# LED_letter_H.net
KiCad netlist of a schematic drawn in EAGLE
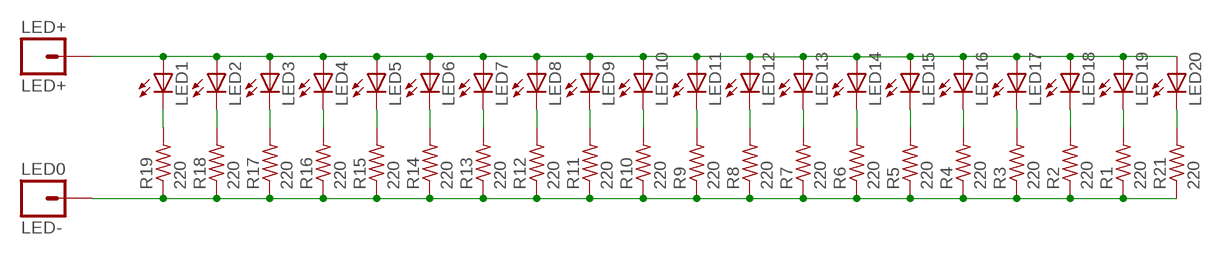
[diagram p0: schematic, sheet 1]

(export (version "E")
  (design (tool "Eeschema 10.0.6"))
  (components
    (comp (ref "LED+")
      (value "LED+")
      (footprint "eagle-import:1X01_OFFSET")
      (libsource (lib "eagle-import") (part "M01OFFSET"))
    )
    (comp (ref "LED0")
      (value "LED-")
      (footprint "eagle-import:1X01_OFFSET")
      (libsource (lib "eagle-import") (part "M01OFFSET"))
    )
    (comp (ref "LED1")
      (value "LED5MM")
      (footprint "eagle-import:LED5MM")
      (libsource (lib "eagle-import") (part "LED5MM"))
    )
    (comp (ref "LED2")
      (value "LED5MM")
      (footprint "eagle-import:LED5MM")
      (libsource (lib "eagle-import") (part "LED5MM"))
    )
    (comp (ref "LED3")
      (value "LED5MM")
      (footprint "eagle-import:LED5MM")
      (libsource (lib "eagle-import") (part "LED5MM"))
    )
    (comp (ref "LED4")
      (value "LED5MM")
      (footprint "eagle-import:LED5MM")
      (libsource (lib "eagle-import") (part "LED5MM"))
    )
    (comp (ref "LED5")
      (value "LED5MM")
      (footprint "eagle-import:LED5MM")
      (libsource (lib "eagle-import") (part "LED5MM"))
    )
    (comp (ref "LED6")
      (value "LED5MM")
      (footprint "eagle-import:LED5MM")
      (libsource (lib "eagle-import") (part "LED5MM"))
    )
    (comp (ref "LED7")
      (value "LED5MM")
      (footprint "eagle-import:LED5MM")
      (libsource (lib "eagle-import") (part "LED5MM"))
    )
    (comp (ref "LED8")
      (value "LED5MM")
      (footprint "eagle-import:LED5MM")
      (libsource (lib "eagle-import") (part "LED5MM"))
    )
    (comp (ref "LED9")
      (value "LED5MM")
      (footprint "eagle-import:LED5MM")
      (libsource (lib "eagle-import") (part "LED5MM"))
    )
    (comp (ref "LED10")
      (value "LED5MM")
      (footprint "eagle-import:LED5MM")
      (libsource (lib "eagle-import") (part "LED5MM"))
    )
    (comp (ref "LED11")
      (value "LED5MM")
      (footprint "eagle-import:LED5MM")
      (libsource (lib "eagle-import") (part "LED5MM"))
    )
    (comp (ref "LED12")
      (value "LED5MM")
      (footprint "eagle-import:LED5MM")
      (libsource (lib "eagle-import") (part "LED5MM"))
    )
    (comp (ref "LED13")
      (value "LED5MM")
      (footprint "eagle-import:LED5MM")
      (libsource (lib "eagle-import") (part "LED5MM"))
    )
    (comp (ref "LED14")
      (value "LED5MM")
      (footprint "eagle-import:LED5MM")
      (libsource (lib "eagle-import") (part "LED5MM"))
    )
    (comp (ref "LED15")
      (value "LED5MM")
      (footprint "eagle-import:LED5MM")
      (libsource (lib "eagle-import") (part "LED5MM"))
    )
    (comp (ref "LED16")
      (value "LED5MM")
      (footprint "eagle-import:LED5MM")
      (libsource (lib "eagle-import") (part "LED5MM"))
    )
    (comp (ref "LED17")
      (value "LED5MM")
      (footprint "eagle-import:LED5MM")
      (libsource (lib "eagle-import") (part "LED5MM"))
    )
    (comp (ref "LED18")
      (value "LED5MM")
      (footprint "eagle-import:LED5MM")
      (libsource (lib "eagle-import") (part "LED5MM"))
    )
    (comp (ref "LED19")
      (value "LED5MM")
      (footprint "eagle-import:LED5MM")
      (libsource (lib "eagle-import") (part "LED5MM"))
    )
    (comp (ref "LED20")
      (value "LED5MM")
      (footprint "eagle-import:LED5MM")
      (libsource (lib "eagle-import") (part "LED5MM"))
    )
    (comp (ref "R1")
      (value "220")
      (footprint "eagle-import:0207_10")
      (libsource (lib "eagle-import") (part "R-US_0207/10"))
    )
    (comp (ref "R2")
      (value "220")
      (footprint "eagle-import:0207_10")
      (libsource (lib "eagle-import") (part "R-US_0207/10"))
    )
    (comp (ref "R3")
      (value "220")
      (footprint "eagle-import:0207_10")
      (libsource (lib "eagle-import") (part "R-US_0207/10"))
    )
    (comp (ref "R4")
      (value "220")
      (footprint "eagle-import:0207_10")
      (libsource (lib "eagle-import") (part "R-US_0207/10"))
    )
    (comp (ref "R5")
      (value "220")
      (footprint "eagle-import:0207_10")
      (libsource (lib "eagle-import") (part "R-US_0207/10"))
    )
    (comp (ref "R6")
      (value "220")
      (footprint "eagle-import:0207_10")
      (libsource (lib "eagle-import") (part "R-US_0207/10"))
    )
    (comp (ref "R7")
      (value "220")
      (footprint "eagle-import:0207_10")
      (libsource (lib "eagle-import") (part "R-US_0207/10"))
    )
    (comp (ref "R8")
      (value "220")
      (footprint "eagle-import:0207_10")
      (libsource (lib "eagle-import") (part "R-US_0207/10"))
    )
    (comp (ref "R9")
      (value "220")
      (footprint "eagle-import:0207_10")
      (libsource (lib "eagle-import") (part "R-US_0207/10"))
    )
    (comp (ref "R10")
      (value "220")
      (footprint "eagle-import:0207_10")
      (libsource (lib "eagle-import") (part "R-US_0207/10"))
    )
    (comp (ref "R11")
      (value "220")
      (footprint "eagle-import:0207_10")
      (libsource (lib "eagle-import") (part "R-US_0207/10"))
    )
    (comp (ref "R12")
      (value "220")
      (footprint "eagle-import:0207_10")
      (libsource (lib "eagle-import") (part "R-US_0207/10"))
    )
    (comp (ref "R13")
      (value "220")
      (footprint "eagle-import:0207_10")
      (libsource (lib "eagle-import") (part "R-US_0207/10"))
    )
    (comp (ref "R14")
      (value "220")
      (footprint "eagle-import:0207_10")
      (libsource (lib "eagle-import") (part "R-US_0207/10"))
    )
    (comp (ref "R15")
      (value "220")
      (footprint "eagle-import:0207_10")
      (libsource (lib "eagle-import") (part "R-US_0207/10"))
    )
    (comp (ref "R16")
      (value "220")
      (footprint "eagle-import:0207_10")
      (libsource (lib "eagle-import") (part "R-US_0207/10"))
    )
    (comp (ref "R17")
      (value "220")
      (footprint "eagle-import:0207_10")
      (libsource (lib "eagle-import") (part "R-US_0207/10"))
    )
    (comp (ref "R18")
      (value "220")
      (footprint "eagle-import:0207_10")
      (libsource (lib "eagle-import") (part "R-US_0207/10"))
    )
    (comp (ref "R19")
      (value "220")
      (footprint "eagle-import:0207_10")
      (libsource (lib "eagle-import") (part "R-US_0207/10"))
    )
    (comp (ref "R21")
      (value "220")
      (footprint "eagle-import:0207_10")
      (libsource (lib "eagle-import") (part "R-US_0207/10"))
    )
  )
  (nets
    (net (code "1") (name "Net-(LED+-Pad1)") (class "Default")
      (node (ref "LED+") (pin "1") (pinfunction "1_1") (pintype "passive"))
      (node (ref "LED1") (pin "A") (pinfunction "A_A") (pintype "passive"))
      (node (ref "LED10") (pin "A") (pinfunction "A_A") (pintype "passive"))
      (node (ref "LED11") (pin "A") (pinfunction "A_A") (pintype "passive"))
      (node (ref "LED12") (pin "A") (pinfunction "A_A") (pintype "passive"))
      (node (ref "LED13") (pin "A") (pinfunction "A_A") (pintype "passive"))
      (node (ref "LED14") (pin "A") (pinfunction "A_A") (pintype "passive"))
      (node (ref "LED15") (pin "A") (pinfunction "A_A") (pintype "passive"))
      (node (ref "LED16") (pin "A") (pinfunction "A_A") (pintype "passive"))
      (node (ref "LED17") (pin "A") (pinfunction "A_A") (pintype "passive"))
      (node (ref "LED18") (pin "A") (pinfunction "A_A") (pintype "passive"))
      (node (ref "LED19") (pin "A") (pinfunction "A_A") (pintype "passive"))
      (node (ref "LED2") (pin "A") (pinfunction "A_A") (pintype "passive"))
      (node (ref "LED20") (pin "A") (pinfunction "A_A") (pintype "passive"))
      (node (ref "LED3") (pin "A") (pinfunction "A_A") (pintype "passive"))
      (node (ref "LED4") (pin "A") (pinfunction "A_A") (pintype "passive"))
      (node (ref "LED5") (pin "A") (pinfunction "A_A") (pintype "passive"))
      (node (ref "LED6") (pin "A") (pinfunction "A_A") (pintype "passive"))
      (node (ref "LED7") (pin "A") (pinfunction "A_A") (pintype "passive"))
      (node (ref "LED8") (pin "A") (pinfunction "A_A") (pintype "passive"))
      (node (ref "LED9") (pin "A") (pinfunction "A_A") (pintype "passive"))
    )
    (net (code "2") (name "Net-(LED0-Pad1)") (class "Default")
      (node (ref "LED0") (pin "1") (pinfunction "1_1") (pintype "passive"))
      (node (ref "R1") (pin "1") (pinfunction "1_1") (pintype "passive"))
      (node (ref "R10") (pin "1") (pinfunction "1_1") (pintype "passive"))
      (node (ref "R11") (pin "1") (pinfunction "1_1") (pintype "passive"))
      (node (ref "R12") (pin "1") (pinfunction "1_1") (pintype "passive"))
      (node (ref "R13") (pin "1") (pinfunction "1_1") (pintype "passive"))
      (node (ref "R14") (pin "1") (pinfunction "1_1") (pintype "passive"))
      (node (ref "R15") (pin "1") (pinfunction "1_1") (pintype "passive"))
      (node (ref "R16") (pin "1") (pinfunction "1_1") (pintype "passive"))
      (node (ref "R17") (pin "1") (pinfunction "1_1") (pintype "passive"))
      (node (ref "R18") (pin "1") (pinfunction "1_1") (pintype "passive"))
      (node (ref "R19") (pin "1") (pinfunction "1_1") (pintype "passive"))
      (node (ref "R2") (pin "1") (pinfunction "1_1") (pintype "passive"))
      (node (ref "R21") (pin "1") (pinfunction "1_1") (pintype "passive"))
      (node (ref "R3") (pin "1") (pinfunction "1_1") (pintype "passive"))
      (node (ref "R4") (pin "1") (pinfunction "1_1") (pintype "passive"))
      (node (ref "R5") (pin "1") (pinfunction "1_1") (pintype "passive"))
      (node (ref "R6") (pin "1") (pinfunction "1_1") (pintype "passive"))
      (node (ref "R7") (pin "1") (pinfunction "1_1") (pintype "passive"))
      (node (ref "R8") (pin "1") (pinfunction "1_1") (pintype "passive"))
      (node (ref "R9") (pin "1") (pinfunction "1_1") (pintype "passive"))
    )
    (net (code "3") (name "Net-(LED1-C)") (class "Default")
      (node (ref "LED1") (pin "K") (pinfunction "C_K") (pintype "passive"))
      (node (ref "R19") (pin "2") (pinfunction "2_2") (pintype "passive"))
    )
    (net (code "4") (name "Net-(LED2-C)") (class "Default")
      (node (ref "LED2") (pin "K") (pinfunction "C_K") (pintype "passive"))
      (node (ref "R18") (pin "2") (pinfunction "2_2") (pintype "passive"))
    )
    (net (code "5") (name "Net-(LED3-C)") (class "Default")
      (node (ref "LED3") (pin "K") (pinfunction "C_K") (pintype "passive"))
      (node (ref "R17") (pin "2") (pinfunction "2_2") (pintype "passive"))
    )
    (net (code "6") (name "Net-(LED4-C)") (class "Default")
      (node (ref "LED4") (pin "K") (pinfunction "C_K") (pintype "passive"))
      (node (ref "R16") (pin "2") (pinfunction "2_2") (pintype "passive"))
    )
    (net (code "7") (name "Net-(LED5-C)") (class "Default")
      (node (ref "LED5") (pin "K") (pinfunction "C_K") (pintype "passive"))
      (node (ref "R15") (pin "2") (pinfunction "2_2") (pintype "passive"))
    )
    (net (code "8") (name "Net-(LED6-C)") (class "Default")
      (node (ref "LED6") (pin "K") (pinfunction "C_K") (pintype "passive"))
      (node (ref "R14") (pin "2") (pinfunction "2_2") (pintype "passive"))
    )
    (net (code "9") (name "Net-(LED7-C)") (class "Default")
      (node (ref "LED7") (pin "K") (pinfunction "C_K") (pintype "passive"))
      (node (ref "R13") (pin "2") (pinfunction "2_2") (pintype "passive"))
    )
    (net (code "10") (name "Net-(LED8-C)") (class "Default")
      (node (ref "LED8") (pin "K") (pinfunction "C_K") (pintype "passive"))
      (node (ref "R12") (pin "2") (pinfunction "2_2") (pintype "passive"))
    )
    (net (code "11") (name "Net-(LED9-C)") (class "Default")
      (node (ref "LED9") (pin "K") (pinfunction "C_K") (pintype "passive"))
      (node (ref "R11") (pin "2") (pinfunction "2_2") (pintype "passive"))
    )
    (net (code "12") (name "Net-(LED10-C)") (class "Default")
      (node (ref "LED10") (pin "K") (pinfunction "C_K") (pintype "passive"))
      (node (ref "R10") (pin "2") (pinfunction "2_2") (pintype "passive"))
    )
    (net (code "13") (name "Net-(LED11-C)") (class "Default")
      (node (ref "LED11") (pin "K") (pinfunction "C_K") (pintype "passive"))
      (node (ref "R9") (pin "2") (pinfunction "2_2") (pintype "passive"))
    )
    (net (code "14") (name "Net-(LED12-C)") (class "Default")
      (node (ref "LED12") (pin "K") (pinfunction "C_K") (pintype "passive"))
      (node (ref "R8") (pin "2") (pinfunction "2_2") (pintype "passive"))
    )
    (net (code "15") (name "Net-(LED13-C)") (class "Default")
      (node (ref "LED13") (pin "K") (pinfunction "C_K") (pintype "passive"))
      (node (ref "R7") (pin "2") (pinfunction "2_2") (pintype "passive"))
    )
    (net (code "16") (name "Net-(LED14-C)") (class "Default")
      (node (ref "LED14") (pin "K") (pinfunction "C_K") (pintype "passive"))
      (node (ref "R6") (pin "2") (pinfunction "2_2") (pintype "passive"))
    )
    (net (code "17") (name "Net-(LED15-C)") (class "Default")
      (node (ref "LED15") (pin "K") (pinfunction "C_K") (pintype "passive"))
      (node (ref "R5") (pin "2") (pinfunction "2_2") (pintype "passive"))
    )
    (net (code "18") (name "Net-(LED16-C)") (class "Default")
      (node (ref "LED16") (pin "K") (pinfunction "C_K") (pintype "passive"))
      (node (ref "R4") (pin "2") (pinfunction "2_2") (pintype "passive"))
    )
    (net (code "19") (name "Net-(LED17-C)") (class "Default")
      (node (ref "LED17") (pin "K") (pinfunction "C_K") (pintype "passive"))
      (node (ref "R3") (pin "2") (pinfunction "2_2") (pintype "passive"))
    )
    (net (code "20") (name "Net-(LED18-C)") (class "Default")
      (node (ref "LED18") (pin "K") (pinfunction "C_K") (pintype "passive"))
      (node (ref "R2") (pin "2") (pinfunction "2_2") (pintype "passive"))
    )
    (net (code "21") (name "Net-(LED19-C)") (class "Default")
      (node (ref "LED19") (pin "K") (pinfunction "C_K") (pintype "passive"))
      (node (ref "R1") (pin "2") (pinfunction "2_2") (pintype "passive"))
    )
    (net (code "22") (name "Net-(LED20-C)") (class "Default")
      (node (ref "LED20") (pin "K") (pinfunction "C_K") (pintype "passive"))
      (node (ref "R21") (pin "2") (pinfunction "2_2") (pintype "passive"))
    )
  )
)
